# FOTA_MicroController_Power_Trigger.net
KiCad netlist of a schematic drawn in Altium Designer
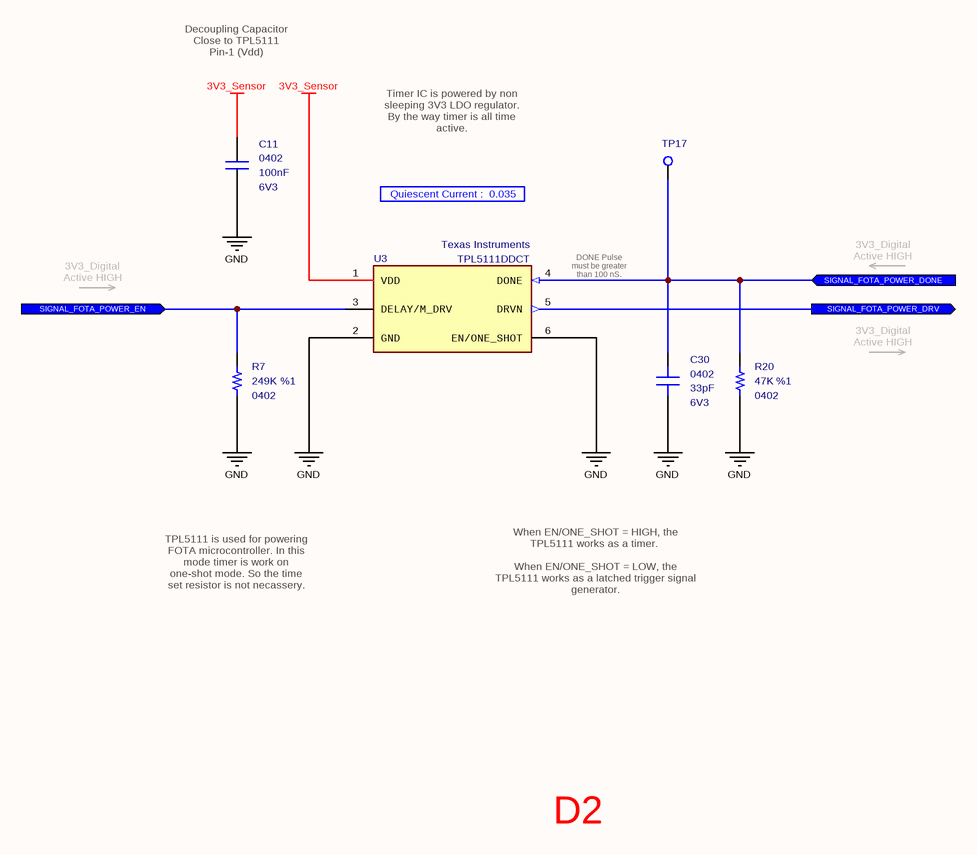
[diagram p0: FOTA MicroController Power Trigger.SchDoc]

(export (version "E")
  (design (tool "Eeschema 10.0.6"))
  (components
    (comp (ref "C11")
      (value "100nF")
      (footprint "CAPACITOR_0402")
      (description "Capacitor - 100nF [0402-6V3] (Ceramic)")
      (fields
        (field (name "MANUFACTURER_PART_NUMBER") "04026D104KAT4A")
        (field (name "MOUSER_PART_NUMBER") "581-04026D104KAT4A")
        (field (name "CASE") "0402")
        (field (name "VOLTAGE") "6V3")
      )
      (libsource (lib "Ovoo_Schematic") (part "Capacitor - 100nF [0402-6V3]"))
    )
    (comp (ref "C30")
      (value "33pF")
      (footprint "CAPACITOR_0402")
      (description "Capacitor - 33pF [0402] (Ceramic)")
      (fields
        (field (name "MANUFACTURER_PART_NUMBER") "C0402C330J9RACAUTO")
        (field (name "MOUSER_PART_NUMBER") "80-C0402C330J9RAUTO")
        (field (name "CASE") "0402")
        (field (name "VOLTAGE") "6V3")
      )
      (libsource (lib "Ovoo_Schematic") (part "Capacitor - 33pF [0402-6V3]"))
    )
    (comp (ref "R7")
      (value "249K")
      (footprint "RESISTOR_0402")
      (description "Thick Film Resistors - SMD 1/16 W 249 Kohms 1%")
      (fields
        (field (name "MANUFACTURER_PART_NUMBER") "CRCW0402249KFKED")
        (field (name "MOUSER_PART_NUMBER") "71-CRCW0402-249K-E3")
        (field (name "TOLERANCE") "%1")
        (field (name "CASE") "0402")
      )
      (libsource (lib "Ovoo_Schematic") (part "Resistor - 249K"))
    )
    (comp (ref "R20")
      (value "47K")
      (footprint "RESISTOR_0402")
      (description "Thick Film Resistors - SMD 1/16 W 47 Kohms 1%")
      (fields
        (field (name "MANUFACTURER_PART_NUMBER") "CRCW040247K0FKED")
        (field (name "MOUSER_PART_NUMBER") "71-CRCW0402-47K-E3")
        (field (name "TOLERANCE") "%1")
        (field (name "CASE") "0402")
      )
      (libsource (lib "Ovoo_Schematic") (part "Resistor - 47K"))
    )
    (comp (ref "TP17")
      (value "PCB - Test Point")
      (footprint "Test_Pad - Hole")
      (description "Test Point")
      (libsource (lib "Ovoo_Schematic") (part "PCB - Test Point"))
    )
    (comp (ref "U3")
      (value "Nanopower Timer IC")
      (footprint "SOT-23-6")
      (fields
        (field (name "MOUSER_PART_NUMBER") "595-TPL5111DDCT")
        (field (name "MANUFACTURER _PART_NUMBER") "TPL5111DDCT")
        (field (name "MANUFACTURER_NAME") "Texas Instruments")
      )
      (libsource (lib "Ovoo_Schematic") (part "IC - TPL5111"))
    )
  )
  (nets
    (net (code "1") (name "/SIGNAL_FOTA_POWER_DONE") (class "Default")
      (node (ref "C30") (pin "2") (pinfunction "2_2") (pintype "passive"))
      (node (ref "R20") (pin "2") (pinfunction "2_2") (pintype "passive"))
      (node (ref "TP17") (pin "1") (pinfunction "1_1") (pintype "passive"))
      (node (ref "U3") (pin "4") (pinfunction "DONE_4") (pintype "input"))
    )
    (net (code "2") (name "/SIGNAL_FOTA_POWER_DRV") (class "Default")
      (node (ref "U3") (pin "5") (pinfunction "DRVN_5") (pintype "output"))
    )
    (net (code "3") (name "/SIGNAL_FOTA_POWER_EN") (class "Default")
      (node (ref "R7") (pin "2") (pinfunction "2_2") (pintype "passive"))
      (node (ref "U3") (pin "3") (pinfunction "DELAY/M_DRV_3") (pintype "passive"))
    )
    (net (code "4") (name "3V3_Sensor") (class "Default")
      (node (ref "C11") (pin "2") (pinfunction "2_2") (pintype "passive"))
      (node (ref "U3") (pin "1") (pinfunction "VDD_1") (pintype "power_in"))
    )
    (net (code "5") (name "GND") (class "Default")
      (node (ref "C11") (pin "1") (pinfunction "1_1") (pintype "passive"))
      (node (ref "C30") (pin "1") (pinfunction "1_1") (pintype "passive"))
      (node (ref "R20") (pin "1") (pinfunction "1_1") (pintype "passive"))
      (node (ref "R7") (pin "1") (pinfunction "1_1") (pintype "passive"))
      (node (ref "U3") (pin "2") (pinfunction "GND_2") (pintype "power_in"))
      (node (ref "U3") (pin "6") (pinfunction "EN/ONE_SHOT_6") (pintype "passive"))
    )
  )
)
